# SX2PC_free_v2-2.net
KiCad netlist of a schematic drawn in EAGLE
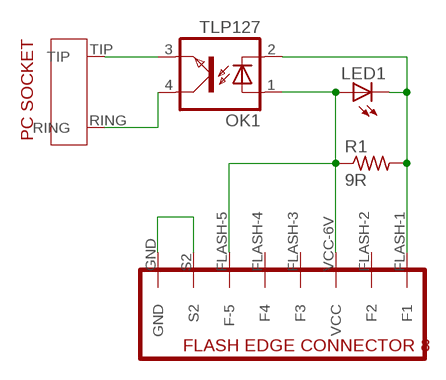
[diagram p0: schematic, sheet 1]

(export (version "E")
  (design (tool "Eeschema 10.0.6"))
  (components
    (comp (ref "LED1")
      (value "LEDCHIP-LED0805")
      (footprint "eagle-import:CHIP-LED0805")
      (libsource (lib "eagle-import") (part "LEDCHIP-LED0805"))
    )
    (comp (ref "OK1")
      (value "TLP127")
      (footprint "eagle-import:SO-4")
      (libsource (lib "eagle-import") (part "TLP127"))
    )
    (comp (ref "R1")
      (value "9R")
      (footprint "eagle-import:R0603")
      (libsource (lib "eagle-import") (part "R-US_R0603"))
    )
    (comp (ref "U$1")
      (value "SX70-FLASH-EDGE8-MALE")
      (footprint "eagle-import:SX70-FLASH-EDGE8")
      (libsource (lib "eagle-import") (part "SX70-FLASH-EDGE8-MALE"))
    )
    (comp (ref "U$2")
      (value "PC-SOCKET-KAISER-1311")
      (footprint "eagle-import:PC-SOCKET-KAISER-1311")
      (libsource (lib "eagle-import") (part "PC-SOCKET-KAISER-1311"))
    )
  )
  (nets
    (net (code "1") (name "Net-(OK1-A)") (class "Default")
      (node (ref "LED1") (pin "A") (pinfunction "A_A") (pintype "passive"))
      (node (ref "OK1") (pin "1") (pinfunction "A_1") (pintype "passive"))
      (node (ref "R1") (pin "1") (pinfunction "1_1") (pintype "passive"))
      (node (ref "U$1") (pin "FLASH-5") (pinfunction "F-5_FLASH-5") (pintype "bidirectional"))
      (node (ref "U$1") (pin "VCC-6V") (pinfunction "VCC_VCC-6V") (pintype "bidirectional"))
    )
    (net (code "2") (name "Net-(OK1-C)") (class "Default")
      (node (ref "LED1") (pin "C") (pinfunction "C_C") (pintype "passive"))
      (node (ref "OK1") (pin "2") (pinfunction "C_2") (pintype "passive"))
      (node (ref "R1") (pin "2") (pinfunction "2_2") (pintype "passive"))
      (node (ref "U$1") (pin "FLASH-1") (pinfunction "F1_FLASH-1") (pintype "bidirectional"))
    )
    (net (code "3") (name "Net-(OK1-COL)") (class "Default")
      (node (ref "OK1") (pin "4") (pinfunction "COL_4") (pintype "passive"))
      (node (ref "U$2") (pin "RING") (pinfunction "RING_RING") (pintype "bidirectional"))
    )
    (net (code "4") (name "Net-(OK1-EMIT)") (class "Default")
      (node (ref "OK1") (pin "3") (pinfunction "EMIT_3") (pintype "passive"))
      (node (ref "U$2") (pin "TIP") (pinfunction "TIP_TIP") (pintype "bidirectional"))
    )
    (net (code "5") (name "Net-(U$1-PadGND)") (class "Default")
      (node (ref "U$1") (pin "GND") (pinfunction "GND_GND") (pintype "bidirectional"))
      (node (ref "U$1") (pin "S2") (pinfunction "S2_S2") (pintype "bidirectional"))
    )
    (net (code "6") (name "unconnected-(U$1-F2-PadFLASH-2)") (class "Default")
      (node (ref "U$1") (pin "FLASH-2") (pinfunction "F2_FLASH-2") (pintype "bidirectional"))
    )
    (net (code "7") (name "unconnected-(U$1-F3-PadFLASH-3)") (class "Default")
      (node (ref "U$1") (pin "FLASH-3") (pinfunction "F3_FLASH-3") (pintype "bidirectional"))
    )
    (net (code "8") (name "unconnected-(U$1-F4-PadFLASH-4)") (class "Default")
      (node (ref "U$1") (pin "FLASH-4") (pinfunction "F4_FLASH-4") (pintype "bidirectional"))
    )
  )
)
